# Postmaster.net
KiCad netlist of a schematic drawn in EAGLE
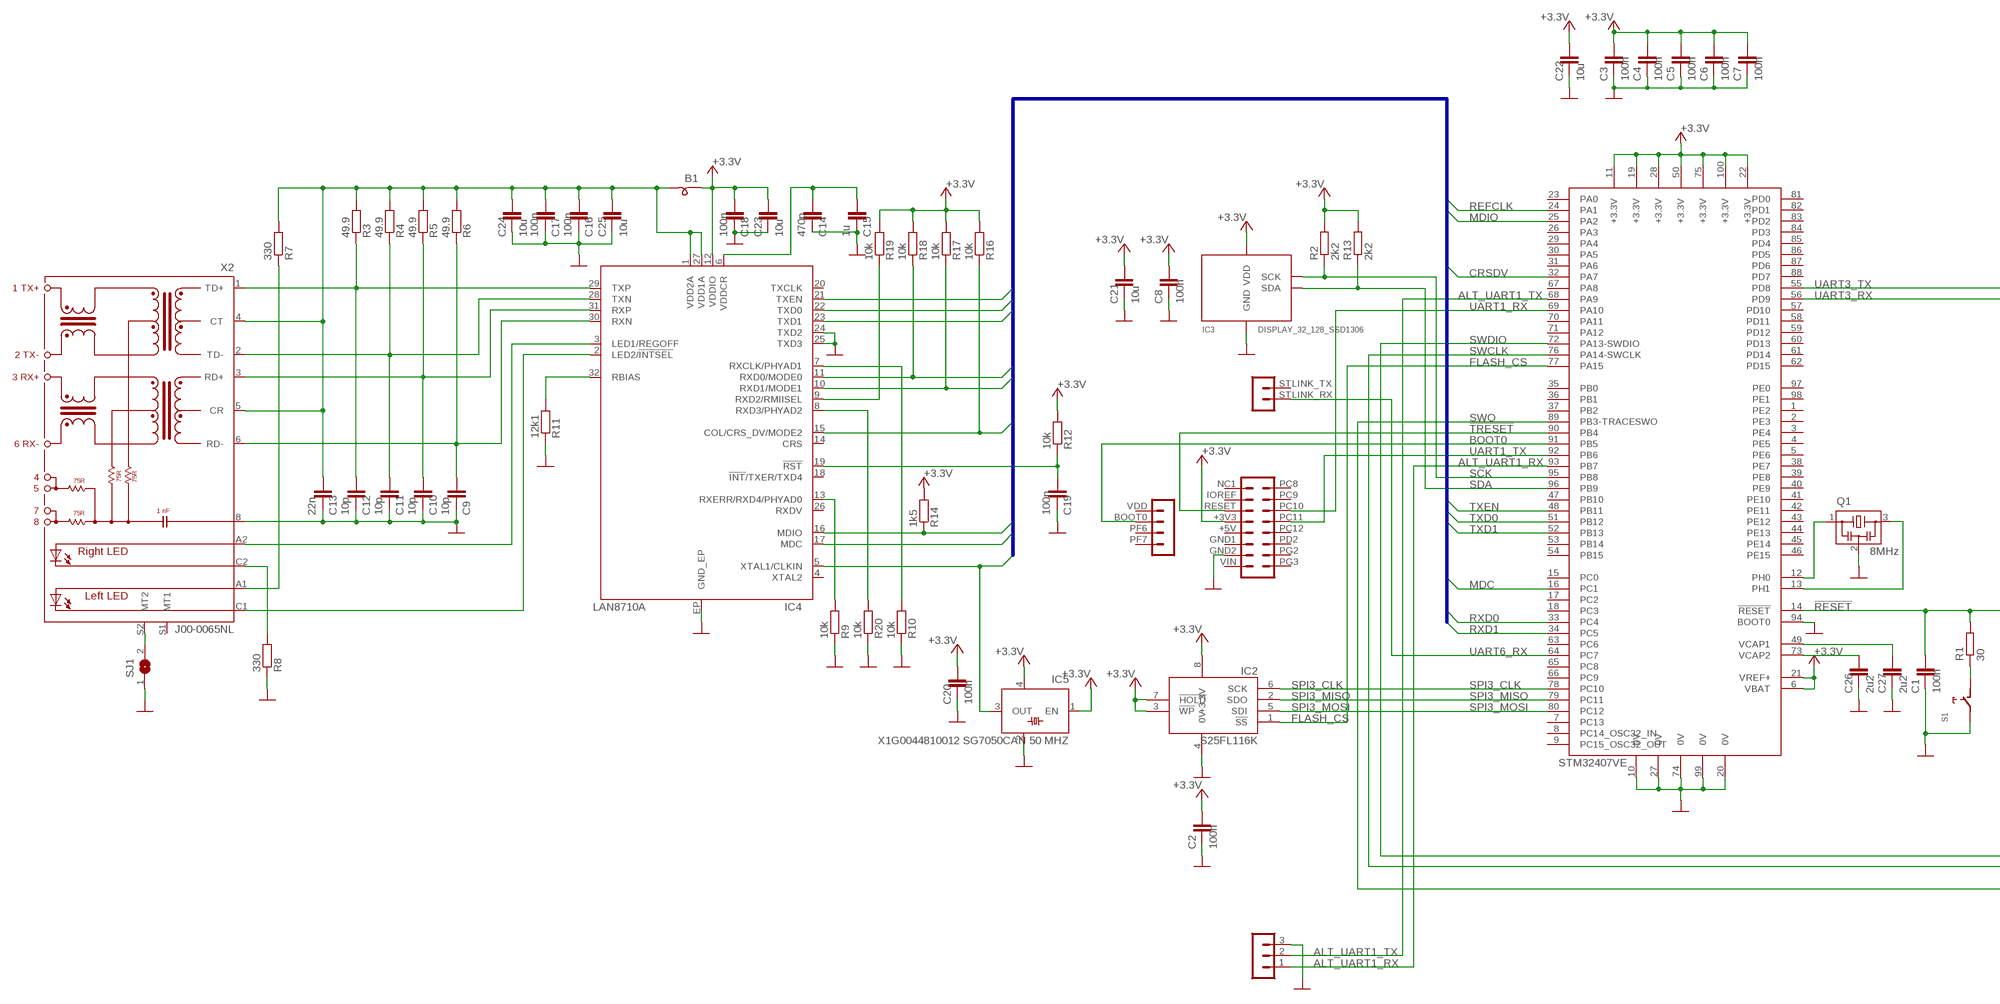
[diagram p0: schematic, sheet 1, part 1 of 2]
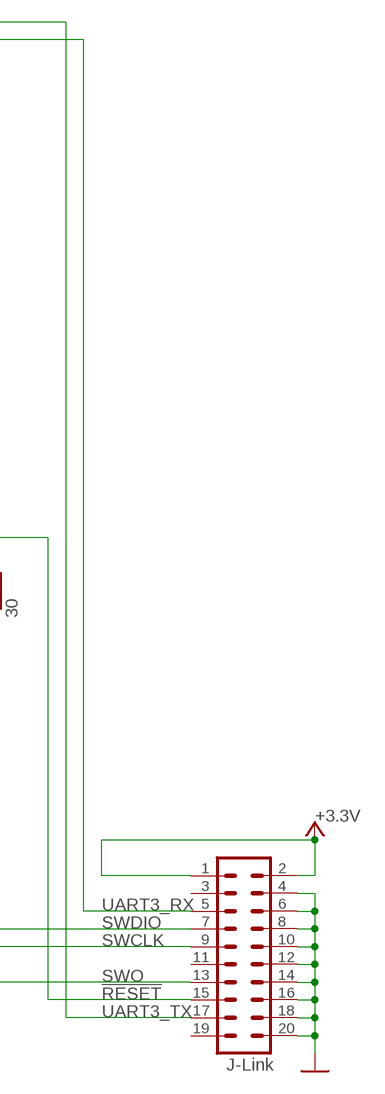
[diagram p1: schematic, sheet 1, part 2 of 2]

(export (version "E")
  (design (tool "Eeschema 10.0.6"))
  (components
    (comp (ref "B1")
      (value "BEADSMD")
      (footprint "eagle-import:0805")
      (libsource (lib "eagle-import") (part "BEADSMD"))
    )
    (comp (ref "C1")
      (value "100n")
      (footprint "eagle-import:0805")
      (libsource (lib "eagle-import") (part "CAPACITOR0805"))
    )
    (comp (ref "C2")
      (value "100n")
      (footprint "eagle-import:0805")
      (libsource (lib "eagle-import") (part "CAPACITOR0805"))
    )
    (comp (ref "C3")
      (value "100n")
      (footprint "eagle-import:0805")
      (libsource (lib "eagle-import") (part "CAPACITOR0805"))
    )
    (comp (ref "C4")
      (value "100n")
      (footprint "eagle-import:0805")
      (libsource (lib "eagle-import") (part "CAPACITOR0805"))
    )
    (comp (ref "C5")
      (value "100n")
      (footprint "eagle-import:0805")
      (libsource (lib "eagle-import") (part "CAPACITOR0805"))
    )
    (comp (ref "C6")
      (value "100n")
      (footprint "eagle-import:0805")
      (libsource (lib "eagle-import") (part "CAPACITOR0805"))
    )
    (comp (ref "C7")
      (value "100n")
      (footprint "eagle-import:0805")
      (libsource (lib "eagle-import") (part "CAPACITOR0805"))
    )
    (comp (ref "C8")
      (value "100n")
      (footprint "eagle-import:0805")
      (libsource (lib "eagle-import") (part "CAPACITOR0805"))
    )
    (comp (ref "C9")
      (value "10p")
      (footprint "eagle-import:0805")
      (libsource (lib "eagle-import") (part "CAPACITOR0805"))
    )
    (comp (ref "C10")
      (value "10p")
      (footprint "eagle-import:0805")
      (libsource (lib "eagle-import") (part "CAPACITOR0805"))
    )
    (comp (ref "C11")
      (value "10p")
      (footprint "eagle-import:0805")
      (libsource (lib "eagle-import") (part "CAPACITOR0805"))
    )
    (comp (ref "C12")
      (value "10p")
      (footprint "eagle-import:0805")
      (libsource (lib "eagle-import") (part "CAPACITOR0805"))
    )
    (comp (ref "C13")
      (value "22n")
      (footprint "eagle-import:0805")
      (libsource (lib "eagle-import") (part "CAPACITOR0805"))
    )
    (comp (ref "C14")
      (value "470p")
      (footprint "eagle-import:0805")
      (libsource (lib "eagle-import") (part "CAPACITOR0805"))
    )
    (comp (ref "C15")
      (value "1u")
      (footprint "eagle-import:0805")
      (libsource (lib "eagle-import") (part "CAPACITOR0805"))
    )
    (comp (ref "C16")
      (value "100n")
      (footprint "eagle-import:0805")
      (libsource (lib "eagle-import") (part "CAPACITOR0805"))
    )
    (comp (ref "C17")
      (value "100n")
      (footprint "eagle-import:0805")
      (libsource (lib "eagle-import") (part "CAPACITOR0805"))
    )
    (comp (ref "C18")
      (value "100n")
      (footprint "eagle-import:0805")
      (libsource (lib "eagle-import") (part "CAPACITOR0805"))
    )
    (comp (ref "C19")
      (value "100n")
      (footprint "eagle-import:0805")
      (libsource (lib "eagle-import") (part "CAPACITOR0805"))
    )
    (comp (ref "C20")
      (value "100n")
      (footprint "eagle-import:0805")
      (libsource (lib "eagle-import") (part "CAPACITOR0805"))
    )
    (comp (ref "C21")
      (value "10u")
      (footprint "eagle-import:0805")
      (libsource (lib "eagle-import") (part "CAPACITOR0805"))
    )
    (comp (ref "C22")
      (value "10u")
      (footprint "eagle-import:0805")
      (libsource (lib "eagle-import") (part "CAPACITOR0805"))
    )
    (comp (ref "C23")
      (value "10u")
      (footprint "eagle-import:0805")
      (libsource (lib "eagle-import") (part "CAPACITOR0805"))
    )
    (comp (ref "C24")
      (value "10u")
      (footprint "eagle-import:0805")
      (libsource (lib "eagle-import") (part "CAPACITOR0805"))
    )
    (comp (ref "C25")
      (value "10u")
      (footprint "eagle-import:0805")
      (libsource (lib "eagle-import") (part "CAPACITOR0805"))
    )
    (comp (ref "C26")
      (value "2u2")
      (footprint "eagle-import:0805")
      (libsource (lib "eagle-import") (part "CAPACITOR0805"))
    )
    (comp (ref "C27")
      (value "2u2")
      (footprint "eagle-import:0805")
      (libsource (lib "eagle-import") (part "CAPACITOR0805"))
    )
    (comp (ref "IC1")
      (value "STM32F407")
      (footprint "eagle-import:TQFP100")
      (libsource (lib "eagle-import") (part "STM32F407"))
    )
    (comp (ref "IC2")
      (value "S25FL116K")
      (footprint "eagle-import:SOIC8-WIDE")
      (libsource (lib "eagle-import") (part "S25FL116KW"))
    )
    (comp (ref "IC3")
      (value "DISPLAY_32_128_SSD1306")
      (footprint "eagle-import:DISPLAY_128_32_SSD1306")
      (libsource (lib "eagle-import") (part "DISPLAY_32_128_SSD1306"))
    )
    (comp (ref "IC4")
      (value "LAN8710A")
      (footprint "eagle-import:QFN32")
      (libsource (lib "eagle-import") (part "LAN8710A"))
    )
    (comp (ref "IC5")
      (value "X1G0044810012 SG7050CAN 50 MHZ")
      (footprint "eagle-import:SM77H")
      (libsource (lib "eagle-import") (part "SM77H"))
    )
    (comp (ref "Q1")
      (value "8MHz")
      (footprint "eagle-import:RESONATOR-SMALL")
      (libsource (lib "eagle-import") (part "RESONATOR-S"))
    )
    (comp (ref "R1")
      (value "30")
      (footprint "eagle-import:0805")
      (libsource (lib "eagle-import") (part "RESISTORR0805"))
    )
    (comp (ref "R2")
      (value "2k2")
      (footprint "eagle-import:0805")
      (libsource (lib "eagle-import") (part "RESISTORR0805"))
    )
    (comp (ref "R3")
      (value "49.9")
      (footprint "eagle-import:0805")
      (libsource (lib "eagle-import") (part "RESISTORR0805"))
    )
    (comp (ref "R4")
      (value "49.9")
      (footprint "eagle-import:0805")
      (libsource (lib "eagle-import") (part "RESISTORR0805"))
    )
    (comp (ref "R5")
      (value "49.9")
      (footprint "eagle-import:0805")
      (libsource (lib "eagle-import") (part "RESISTORR0805"))
    )
    (comp (ref "R6")
      (value "49.9")
      (footprint "eagle-import:0805")
      (libsource (lib "eagle-import") (part "RESISTORR0805"))
    )
    (comp (ref "R7")
      (value "330")
      (footprint "eagle-import:0805")
      (libsource (lib "eagle-import") (part "RESISTORR0805"))
    )
    (comp (ref "R8")
      (value "330")
      (footprint "eagle-import:0805")
      (libsource (lib "eagle-import") (part "RESISTORR0805"))
    )
    (comp (ref "R9")
      (value "10k")
      (footprint "eagle-import:0805")
      (libsource (lib "eagle-import") (part "RESISTORR0805"))
    )
    (comp (ref "R10")
      (value "10k")
      (footprint "eagle-import:0805")
      (libsource (lib "eagle-import") (part "RESISTORR0805"))
    )
    (comp (ref "R11")
      (value "12k1")
      (footprint "eagle-import:0805")
      (libsource (lib "eagle-import") (part "RESISTORR0805"))
    )
    (comp (ref "R12")
      (value "10k")
      (footprint "eagle-import:0805")
      (libsource (lib "eagle-import") (part "RESISTORR0805"))
    )
    (comp (ref "R13")
      (value "2k2")
      (footprint "eagle-import:0805")
      (libsource (lib "eagle-import") (part "RESISTORR0805"))
    )
    (comp (ref "R14")
      (value "1k5")
      (footprint "eagle-import:0805")
      (libsource (lib "eagle-import") (part "RESISTORR0805"))
    )
    (comp (ref "R16")
      (value "10k")
      (footprint "eagle-import:0805")
      (libsource (lib "eagle-import") (part "RESISTORR0805"))
    )
    (comp (ref "R17")
      (value "10k")
      (footprint "eagle-import:0805")
      (libsource (lib "eagle-import") (part "RESISTORR0805"))
    )
    (comp (ref "R18")
      (value "10k")
      (footprint "eagle-import:0805")
      (libsource (lib "eagle-import") (part "RESISTORR0805"))
    )
    (comp (ref "R19")
      (value "10k")
      (footprint "eagle-import:0805")
      (libsource (lib "eagle-import") (part "RESISTORR0805"))
    )
    (comp (ref "R20")
      (value "10k")
      (footprint "eagle-import:0805")
      (libsource (lib "eagle-import") (part "RESISTORR0805"))
    )
    (comp (ref "S1")
      (value "SWITCHSMD")
      (footprint "eagle-import:SWITCH-SMD")
      (libsource (lib "eagle-import") (part "SWITCHSMD"))
    )
    (comp (ref "SJ1") (value "SJ") (footprint "eagle-import:SJ") (libsource (lib "eagle-import") (part "SJ")))
    (comp (ref "U$1")
      (value "NUCLEO-TOPLEFT")
      (footprint "eagle-import:NUCLEO-TOPLEFT")
      (libsource (lib "eagle-import") (part "NUCLEO-TOPLEFT"))
    )
    (comp (ref "U$3")
      (value "HEADER-MALE-3")
      (footprint "eagle-import:HEADER-MALE-3")
      (libsource (lib "eagle-import") (part "HEADER-MALE-3"))
    )
    (comp (ref "X1")
      (value "HEADER-IDC-10-2")
      (footprint "eagle-import:IDC-10_2")
      (libsource (lib "eagle-import") (part "HEADER-IDC-10-2"))
    )
    (comp (ref "X2")
      (value "J00-0065NL")
      (footprint "eagle-import:ETHERNET")
      (libsource (lib "eagle-import") (part "J00-0065NL"))
    )
  )
  (nets
    (net (code "1") (name "+3.3V") (class "Default")
      (node (ref "B1") (pin "1") (pinfunction "1_1") (pintype "passive"))
      (node (ref "C18") (pin "1") (pinfunction "1_1") (pintype "passive"))
      (node (ref "C2") (pin "1") (pinfunction "1_1") (pintype "passive"))
      (node (ref "C20") (pin "1") (pinfunction "1_1") (pintype "passive"))
      (node (ref "C21") (pin "1") (pinfunction "1_1") (pintype "passive"))
      (node (ref "C22") (pin "1") (pinfunction "1_1") (pintype "passive"))
      (node (ref "C23") (pin "1") (pinfunction "1_1") (pintype "passive"))
      (node (ref "C3") (pin "1") (pinfunction "1_1") (pintype "passive"))
      (node (ref "C4") (pin "1") (pinfunction "1_1") (pintype "passive"))
      (node (ref "C5") (pin "1") (pinfunction "1_1") (pintype "passive"))
      (node (ref "C6") (pin "1") (pinfunction "1_1") (pintype "passive"))
      (node (ref "C7") (pin "1") (pinfunction "1_1") (pintype "passive"))
      (node (ref "C8") (pin "1") (pinfunction "1_1") (pintype "passive"))
      (node (ref "IC1") (pin "100") (pinfunction "+3.3V_100") (pintype "power_in"))
      (node (ref "IC1") (pin "11") (pinfunction "+3.3V_11") (pintype "power_in"))
      (node (ref "IC1") (pin "19") (pinfunction "+3.3V_19") (pintype "power_in"))
      (node (ref "IC1") (pin "21") (pinfunction "VREF+_21") (pintype "input"))
      (node (ref "IC1") (pin "22") (pinfunction "+3.3V_22") (pintype "power_in"))
      (node (ref "IC1") (pin "28") (pinfunction "+3.3V_28") (pintype "power_in"))
      (node (ref "IC1") (pin "50") (pinfunction "+3.3V_50") (pintype "power_in"))
      (node (ref "IC1") (pin "6") (pinfunction "VBAT_6") (pintype "input"))
      (node (ref "IC1") (pin "75") (pinfunction "+3.3V_75") (pintype "power_in"))
      (node (ref "IC2") (pin "3") (pinfunction "~{WP}_3") (pintype "passive"))
      (node (ref "IC2") (pin "7") (pinfunction "~{HOLD}_7") (pintype "passive"))
      (node (ref "IC2") (pin "8") (pinfunction "+3.3V_8") (pintype "power_in"))
      (node (ref "IC3") (pin "VCC") (pinfunction "VDD_VCC") (pintype "power_in"))
      (node (ref "IC4") (pin "12") (pinfunction "VDDIO_12") (pintype "power_in"))
      (node (ref "IC5") (pin "1") (pinfunction "EN_1") (pintype "input"))
      (node (ref "IC5") (pin "4") (pinfunction "+3.3V_4") (pintype "power_in"))
      (node (ref "R12") (pin "2") (pinfunction "2_2") (pintype "passive"))
      (node (ref "R13") (pin "2") (pinfunction "2_2") (pintype "passive"))
      (node (ref "R14") (pin "2") (pinfunction "2_2") (pintype "passive"))
      (node (ref "R16") (pin "2") (pinfunction "2_2") (pintype "passive"))
      (node (ref "R17") (pin "2") (pinfunction "2_2") (pintype "passive"))
      (node (ref "R18") (pin "2") (pinfunction "2_2") (pintype "passive"))
      (node (ref "R19") (pin "2") (pinfunction "2_2") (pintype "passive"))
      (node (ref "R2") (pin "2") (pinfunction "2_2") (pintype "passive"))
      (node (ref "U$1") (pin "+3V3") (pinfunction "7_+3V3") (pintype "passive"))
      (node (ref "X1") (pin "1") (pinfunction "1_1") (pintype "passive"))
      (node (ref "X1") (pin "2") (pinfunction "2_2") (pintype "passive"))
    )
    (net (code "2") (name "/ALT_UART1_RX") (class "Default")
      (node (ref "IC1") (pin "93") (pinfunction "PB7_93") (pintype "bidirectional"))
      (node (ref "U$3") (pin "1") (pinfunction "1_1") (pintype "passive"))
    )
    (net (code "3") (name "/ALT_UART1_TX") (class "Default")
      (node (ref "IC1") (pin "68") (pinfunction "PA9_68") (pintype "bidirectional"))
      (node (ref "U$3") (pin "2") (pinfunction "2_2") (pintype "passive"))
    )
    (net (code "4") (name "/BOOT0") (class "Default")
      (node (ref "IC1") (pin "91") (pinfunction "PB5_91") (pintype "bidirectional"))
      (node (ref "U$1") (pin "BOOT0") (pinfunction "2_BOOT0") (pintype "passive"))
    )
    (net (code "5") (name "/CRSDV") (class "Default")
      (node (ref "IC1") (pin "32") (pinfunction "PA7_32") (pintype "bidirectional"))
      (node (ref "IC4") (pin "15") (pinfunction "COL/CRS_DV/MODE2_15") (pintype "bidirectional"))
      (node (ref "R16") (pin "1") (pinfunction "1_1") (pintype "passive"))
    )
    (net (code "6") (name "/FLASH_CS") (class "Default")
      (node (ref "IC1") (pin "77") (pinfunction "PA15_77") (pintype "bidirectional"))
      (node (ref "IC2") (pin "1") (pinfunction "~{SS}_1") (pintype "input"))
    )
    (net (code "7") (name "/MDC") (class "Default")
      (node (ref "IC1") (pin "16") (pinfunction "PC1_16") (pintype "bidirectional"))
      (node (ref "IC4") (pin "17") (pinfunction "MDC_17") (pintype "bidirectional"))
    )
    (net (code "8") (name "/MDIO") (class "Default")
      (node (ref "IC1") (pin "25") (pinfunction "PA2_25") (pintype "bidirectional"))
      (node (ref "IC4") (pin "16") (pinfunction "MDIO_16") (pintype "bidirectional"))
      (node (ref "R14") (pin "1") (pinfunction "1_1") (pintype "passive"))
    )
    (net (code "9") (name "/REFCLK") (class "Default")
      (node (ref "IC1") (pin "24") (pinfunction "PA1_24") (pintype "bidirectional"))
      (node (ref "IC4") (pin "5") (pinfunction "XTAL1/CLKIN_5") (pintype "bidirectional"))
      (node (ref "IC5") (pin "3") (pinfunction "OUT_3") (pintype "output"))
    )
    (net (code "10") (name "/RXD0") (class "Default")
      (node (ref "IC1") (pin "33") (pinfunction "PC4_33") (pintype "bidirectional"))
      (node (ref "IC4") (pin "11") (pinfunction "RXD0/MODE0_11") (pintype "bidirectional"))
      (node (ref "R18") (pin "1") (pinfunction "1_1") (pintype "passive"))
    )
    (net (code "11") (name "/RXD1") (class "Default")
      (node (ref "IC1") (pin "34") (pinfunction "PC5_34") (pintype "bidirectional"))
      (node (ref "IC4") (pin "10") (pinfunction "RXD1/MODE1_10") (pintype "bidirectional"))
      (node (ref "R17") (pin "1") (pinfunction "1_1") (pintype "passive"))
    )
    (net (code "12") (name "/SCK") (class "Default")
      (node (ref "IC1") (pin "95") (pinfunction "PB8_95") (pintype "bidirectional"))
      (node (ref "IC3") (pin "SCK") (pinfunction "SCK_SCK") (pintype "bidirectional"))
      (node (ref "R2") (pin "1") (pinfunction "1_1") (pintype "passive"))
    )
    (net (code "13") (name "/SDA") (class "Default")
      (node (ref "IC1") (pin "96") (pinfunction "PB9_96") (pintype "bidirectional"))
      (node (ref "IC3") (pin "SDA") (pinfunction "SDA_SDA") (pintype "bidirectional"))
      (node (ref "R13") (pin "1") (pinfunction "1_1") (pintype "passive"))
    )
    (net (code "14") (name "/SPI3_CLK") (class "Default")
      (node (ref "IC1") (pin "78") (pinfunction "PC10_78") (pintype "bidirectional"))
      (node (ref "IC2") (pin "6") (pinfunction "SCK_6") (pintype "input"))
    )
    (net (code "15") (name "/SPI3_MISO") (class "Default")
      (node (ref "IC1") (pin "79") (pinfunction "PC11_79") (pintype "bidirectional"))
      (node (ref "IC2") (pin "2") (pinfunction "SDO_2") (pintype "output"))
    )
    (net (code "16") (name "/SPI3_MOSI") (class "Default")
      (node (ref "IC1") (pin "80") (pinfunction "PC12_80") (pintype "bidirectional"))
      (node (ref "IC2") (pin "5") (pinfunction "SDI_5") (pintype "input"))
    )
    (net (code "17") (name "/SWCLK") (class "Default")
      (node (ref "IC1") (pin "76") (pinfunction "PA14-SWCLK_76") (pintype "bidirectional"))
      (node (ref "X1") (pin "9") (pinfunction "9_9") (pintype "passive"))
    )
    (net (code "18") (name "/SWDIO") (class "Default")
      (node (ref "IC1") (pin "72") (pinfunction "PA13-SWDIO_72") (pintype "bidirectional"))
      (node (ref "X1") (pin "7") (pinfunction "7_7") (pintype "passive"))
    )
    (net (code "19") (name "/SWO") (class "Default")
      (node (ref "IC1") (pin "89") (pinfunction "PB3-TRACESWO_89") (pintype "bidirectional"))
      (node (ref "X1") (pin "13") (pinfunction "13_13") (pintype "passive"))
    )
    (net (code "20") (name "/TXD0") (class "Default")
      (node (ref "IC1") (pin "51") (pinfunction "PB12_51") (pintype "bidirectional"))
      (node (ref "IC4") (pin "22") (pinfunction "TXD0_22") (pintype "bidirectional"))
    )
    (net (code "21") (name "/TXD1") (class "Default")
      (node (ref "IC1") (pin "52") (pinfunction "PB13_52") (pintype "bidirectional"))
      (node (ref "IC4") (pin "23") (pinfunction "TXD1_23") (pintype "bidirectional"))
    )
    (net (code "22") (name "/TXEN") (class "Default")
      (node (ref "IC1") (pin "48") (pinfunction "PB11_48") (pintype "bidirectional"))
      (node (ref "IC4") (pin "21") (pinfunction "TXEN_21") (pintype "bidirectional"))
    )
    (net (code "23") (name "/UART1_RX") (class "Default")
      (node (ref "IC1") (pin "69") (pinfunction "PA10_69") (pintype "bidirectional"))
      (node (ref "U$1") (pin "PC10") (pinfunction "6_PC10") (pintype "passive"))
    )
    (net (code "24") (name "/UART1_TX") (class "Default")
      (node (ref "IC1") (pin "92") (pinfunction "PB6_92") (pintype "bidirectional"))
      (node (ref "U$1") (pin "PC11") (pinfunction "8_PC11") (pintype "passive"))
    )
    (net (code "25") (name "/UART3_RX") (class "Default")
      (node (ref "IC1") (pin "56") (pinfunction "PD9_56") (pintype "bidirectional"))
      (node (ref "X1") (pin "5") (pinfunction "5_5") (pintype "passive"))
    )
    (net (code "26") (name "/UART3_TX") (class "Default")
      (node (ref "IC1") (pin "55") (pinfunction "PD8_55") (pintype "bidirectional"))
      (node (ref "X1") (pin "17") (pinfunction "17_17") (pintype "passive"))
    )
    (net (code "27") (name "/UART6_RX") (class "Default")
      (node (ref "IC1") (pin "64") (pinfunction "PC7_64") (pintype "bidirectional"))
      (node (ref "U$1") (pin "STLINK_RX") (pinfunction "1_STLINK_RX") (pintype "passive"))
    )
    (net (code "28") (name "/~{RESET}") (class "Default")
      (node (ref "C1") (pin "1") (pinfunction "1_1") (pintype "passive"))
      (node (ref "IC1") (pin "14") (pinfunction "~{RESET}_14") (pintype "input"))
      (node (ref "R1") (pin "2") (pinfunction "2_2") (pintype "passive"))
      (node (ref "X1") (pin "15") (pinfunction "15_15") (pintype "passive"))
    )
    (net (code "29") (name "/~{TRESET}") (class "Default")
      (node (ref "IC1") (pin "90") (pinfunction "PB4_90") (pintype "bidirectional"))
      (node (ref "U$1") (pin "RESET") (pinfunction "5_RESET") (pintype "passive"))
    )
    (net (code "30") (name "0V") (class "Default")
      (node (ref "C1") (pin "2") (pinfunction "2_2") (pintype "passive"))
      (node (ref "C10") (pin "2") (pinfunction "2_2") (pintype "passive"))
      (node (ref "C11") (pin "2") (pinfunction "2_2") (pintype "passive"))
      (node (ref "C12") (pin "2") (pinfunction "2_2") (pintype "passive"))
      (node (ref "C13") (pin "2") (pinfunction "2_2") (pintype "passive"))
      (node (ref "C14") (pin "2") (pinfunction "2_2") (pintype "passive"))
      (node (ref "C15") (pin "2") (pinfunction "2_2") (pintype "passive"))
      (node (ref "C16") (pin "2") (pinfunction "2_2") (pintype "passive"))
      (node (ref "C17") (pin "2") (pinfunction "2_2") (pintype "passive"))
      (node (ref "C18") (pin "2") (pinfunction "2_2") (pintype "passive"))
      (node (ref "C19") (pin "2") (pinfunction "2_2") (pintype "passive"))
      (node (ref "C2") (pin "2") (pinfunction "2_2") (pintype "passive"))
      (node (ref "C20") (pin "2") (pinfunction "2_2") (pintype "passive"))
      (node (ref "C21") (pin "2") (pinfunction "2_2") (pintype "passive"))
      (node (ref "C22") (pin "2") (pinfunction "2_2") (pintype "passive"))
      (node (ref "C23") (pin "2") (pinfunction "2_2") (pintype "passive"))
      (node (ref "C24") (pin "2") (pinfunction "2_2") (pintype "passive"))
      (node (ref "C25") (pin "2") (pinfunction "2_2") (pintype "passive"))
      (node (ref "C26") (pin "2") (pinfunction "2_2") (pintype "passive"))
      (node (ref "C27") (pin "2") (pinfunction "2_2") (pintype "passive"))
      (node (ref "C3") (pin "2") (pinfunction "2_2") (pintype "passive"))
      (node (ref "C4") (pin "2") (pinfunction "2_2") (pintype "passive"))
      (node (ref "C5") (pin "2") (pinfunction "2_2") (pintype "passive"))
      (node (ref "C6") (pin "2") (pinfunction "2_2") (pintype "passive"))
      (node (ref "C7") (pin "2") (pinfunction "2_2") (pintype "passive"))
      (node (ref "C8") (pin "2") (pinfunction "2_2") (pintype "passive"))
      (node (ref "C9") (pin "2") (pinfunction "2_2") (pintype "passive"))
      (node (ref "IC1") (pin "10") (pinfunction "0V_10") (pintype "power_in"))
      (node (ref "IC1") (pin "20") (pinfunction "0V_20") (pintype "power_in"))
      (node (ref "IC1") (pin "27") (pinfunction "0V_27") (pintype "power_in"))
      (node (ref "IC1") (pin "74") (pinfunction "0V_74") (pintype "power_in"))
      (node (ref "IC1") (pin "94") (pinfunction "BOOT0_94") (pintype "input"))
      (node (ref "IC1") (pin "99") (pinfunction "0V_99") (pintype "power_in"))
      (node (ref "IC2") (pin "4") (pinfunction "0V_4") (pintype "power_in"))
      (node (ref "IC3") (pin "GND") (pinfunction "GND_GND") (pintype "power_in"))
      (node (ref "IC4") (pin "24") (pinfunction "TXD2_24") (pintype "bidirectional"))
      (node (ref "IC4") (pin "25") (pinfunction "TXD3_25") (pintype "bidirectional"))
      (node (ref "IC4") (pin "EP") (pinfunction "GND_EP_EP") (pintype "power_in"))
      (node (ref "IC5") (pin "2") (pinfunction "0V_2") (pintype "power_in"))
      (node (ref "Q1") (pin "2") (pinfunction "2_2") (pintype "passive"))
      (node (ref "R10") (pin "1") (pinfunction "1_1") (pintype "passive"))
      (node (ref "R11") (pin "1") (pinfunction "1_1") (pintype "passive"))
      (node (ref "R20") (pin "1") (pinfunction "1_1") (pintype "passive"))
      (node (ref "R8") (pin "1") (pinfunction "1_1") (pintype "passive"))
      (node (ref "R9") (pin "1") (pinfunction "1_1") (pintype "passive"))
      (node (ref "S1") (pin "3") (pinfunction "2_3") (pintype "passive"))
      (node (ref "S1") (pin "4") (pinfunction "2_4") (pintype "passive"))
      (node (ref "SJ1") (pin "1") (pinfunction "1_1") (pintype "passive"))
      (node (ref "U$1") (pin "GND2") (pinfunction "13_GND2") (pintype "passive"))
      (node (ref "U$3") (pin "3") (pinfunction "3_3") (pintype "passive"))
      (node (ref "X1") (pin "10") (pinfunction "10_10") (pintype "passive"))
      (node (ref "X1") (pin "12") (pinfunction "12_12") (pintype "passive"))
      (node (ref "X1") (pin "14") (pinfunction "14_14") (pintype "passive"))
      (node (ref "X1") (pin "16") (pinfunction "16_16") (pintype "passive"))
      (node (ref "X1") (pin "18") (pinfunction "18_18") (pintype "passive"))
      (node (ref "X1") (pin "20") (pinfunction "20_20") (pintype "passive"))
      (node (ref "X1") (pin "4") (pinfunction "4_4") (pintype "passive"))
      (node (ref "X1") (pin "6") (pinfunction "6_6") (pintype "passive"))
      (node (ref "X1") (pin "8") (pinfunction "8_8") (pintype "passive"))
      (node (ref "X2") (pin "8") (pinfunction "8_8") (pintype "input"))
    )
    (net (code "31") (name "Net-(IC1A-PH0)") (class "Default")
      (node (ref "IC1") (pin "12") (pinfunction "PH0_12") (pintype "bidirectional"))
      (node (ref "Q1") (pin "1") (pinfunction "1_1") (pintype "passive"))
    )
    (net (code "32") (name "Net-(IC1A-PH1)") (class "Default")
      (node (ref "IC1") (pin "13") (pinfunction "PH1_13") (pintype "bidirectional"))
      (node (ref "Q1") (pin "3") (pinfunction "3_3") (pintype "passive"))
    )
    (net (code "33") (name "Net-(IC1A-VCAP1)") (class "Default")
      (node (ref "C27") (pin "1") (pinfunction "1_1") (pintype "passive"))
      (node (ref "IC1") (pin "49") (pinfunction "VCAP1_49") (pintype "bidirectional"))
    )
    (net (code "34") (name "Net-(IC1A-VCAP2)") (class "Default")
      (node (ref "C26") (pin "1") (pinfunction "1_1") (pintype "passive"))
      (node (ref "IC1") (pin "73") (pinfunction "VCAP2_73") (pintype "bidirectional"))
    )
    (net (code "35") (name "Net-(IC4-LED1{slash}REGOFF)") (class "Default")
      (node (ref "IC4") (pin "3") (pinfunction "LED1/REGOFF_3") (pintype "bidirectional"))
      (node (ref "X2") (pin "A2") (pinfunction "A-R_A2") (pintype "passive"))
    )
    (net (code "36") (name "Net-(IC4-LED2{slash}~{INTSEL})") (class "Default")
      (node (ref "IC4") (pin "2") (pinfunction "LED2/~{INTSEL}_2") (pintype "bidirectional"))
      (node (ref "X2") (pin "C1") (pinfunction "C-L_C1") (pintype "passive"))
    )
    (net (code "37") (name "Net-(IC4-RBIAS)") (class "Default")
      (node (ref "IC4") (pin "32") (pinfunction "RBIAS_32") (pintype "bidirectional"))
      (node (ref "R11") (pin "2") (pinfunction "2_2") (pintype "passive"))
    )
    (net (code "38") (name "Net-(IC4-RXCLK{slash}PHYAD1)") (class "Default")
      (node (ref "IC4") (pin "7") (pinfunction "RXCLK/PHYAD1_7") (pintype "bidirectional"))
      (node (ref "R10") (pin "2") (pinfunction "2_2") (pintype "passive"))
    )
    (net (code "39") (name "Net-(IC4-RXD2{slash}RMIISEL)") (class "Default")
      (node (ref "IC4") (pin "9") (pinfunction "RXD2/RMIISEL_9") (pintype "bidirectional"))
      (node (ref "R19") (pin "1") (pinfunction "1_1") (pintype "passive"))
    )
    (net (code "40") (name "Net-(IC4-RXD3{slash}PHYAD2)") (class "Default")
      (node (ref "IC4") (pin "8") (pinfunction "RXD3/PHYAD2_8") (pintype "bidirectional"))
      (node (ref "R20") (pin "2") (pinfunction "2_2") (pintype "passive"))
    )
    (net (code "41") (name "Net-(IC4-RXERR{slash}RXD4{slash}PHYAD0)") (class "Default")
      (node (ref "IC4") (pin "13") (pinfunction "RXERR/RXD4/PHYAD0_13") (pintype "bidirectional"))
      (node (ref "R9") (pin "2") (pinfunction "2_2") (pintype "passive"))
    )
    (net (code "42") (name "Net-(IC4-RXN)") (class "Default")
      (node (ref "C9") (pin "1") (pinfunction "1_1") (pintype "passive"))
      (node (ref "IC4") (pin "30") (pinfunction "RXN_30") (pintype "bidirectional"))
      (node (ref "R6") (pin "1") (pinfunction "1_1") (pintype "passive"))
      (node (ref "X2") (pin "6") (pinfunction "RD-_6") (pintype "input"))
    )
    (net (code "43") (name "Net-(IC4-RXP)") (class "Default")
      (node (ref "C10") (pin "1") (pinfunction "1_1") (pintype "passive"))
      (node (ref "IC4") (pin "31") (pinfunction "RXP_31") (pintype "bidirectional"))
      (node (ref "R5") (pin "1") (pinfunction "1_1") (pintype "passive"))
      (node (ref "X2") (pin "3") (pinfunction "RD+_3") (pintype "input"))
    )
    (net (code "44") (name "Net-(IC4-TXN)") (class "Default")
      (node (ref "C11") (pin "1") (pinfunction "1_1") (pintype "passive"))
      (node (ref "IC4") (pin "28") (pinfunction "TXN_28") (pintype "bidirectional"))
      (node (ref "R4") (pin "1") (pinfunction "1_1") (pintype "passive"))
      (node (ref "X2") (pin "2") (pinfunction "TD-_2") (pintype "input"))
    )
    (net (code "45") (name "Net-(IC4-TXP)") (class "Default")
      (node (ref "C12") (pin "1") (pinfunction "1_1") (pintype "passive"))
      (node (ref "IC4") (pin "29") (pinfunction "TXP_29") (pintype "bidirectional"))
      (node (ref "R3") (pin "1") (pinfunction "1_1") (pintype "passive"))
      (node (ref "X2") (pin "1") (pinfunction "TD+_1") (pintype "input"))
    )
    (net (code "46") (name "Net-(IC4-VDD1A)") (class "Default")
      (node (ref "B1") (pin "2") (pinfunction "2_2") (pintype "passive"))
      (node (ref "C13") (pin "1") (pinfunction "1_1") (pintype "passive"))
      (node (ref "C16") (pin "1") (pinfunction "1_1") (pintype "passive"))
      (node (ref "C17") (pin "1") (pinfunction "1_1") (pintype "passive"))
      (node (ref "C24") (pin "1") (pinfunction "1_1") (pintype "passive"))
      (node (ref "C25") (pin "1") (pinfunction "1_1") (pintype "passive"))
      (node (ref "IC4") (pin "1") (pinfunction "VDD2A_1") (pintype "power_in"))
      (node (ref "IC4") (pin "27") (pinfunction "VDD1A_27") (pintype "power_in"))
      (node (ref "R3") (pin "2") (pinfunction "2_2") (pintype "passive"))
      (node (ref "R4") (pin "2") (pinfunction "2_2") (pintype "passive"))
      (node (ref "R5") (pin "2") (pinfunction "2_2") (pintype "passive"))
      (node (ref "R6") (pin "2") (pinfunction "2_2") (pintype "passive"))
      (node (ref "R7") (pin "2") (pinfunction "2_2") (pintype "passive"))
      (node (ref "X2") (pin "4") (pinfunction "CT_4") (pintype "input"))
      (node (ref "X2") (pin "5") (pinfunction "CR_5") (pintype "input"))
    )
    (net (code "47") (name "Net-(IC4-VDDCR)") (class "Default")
      (node (ref "C14") (pin "1") (pinfunction "1_1") (pintype "passive"))
      (node (ref "C15") (pin "1") (pinfunction "1_1") (pintype "passive"))
      (node (ref "IC4") (pin "6") (pinfunction "VDDCR_6") (pintype "power_in"))
    )
    (net (code "48") (name "Net-(IC4-~{RST})") (class "Default")
      (node (ref "C19") (pin "1") (pinfunction "1_1") (pintype "passive"))
      (node (ref "IC4") (pin "19") (pinfunction "~{RST}_19") (pintype "bidirectional"))
      (node (ref "R12") (pin "1") (pinfunction "1_1") (pintype "passive"))
    )
    (net (code "49") (name "Net-(R1-Pad1)") (class "Default")
      (node (ref "R1") (pin "1") (pinfunction "1_1") (pintype "passive"))
      (node (ref "S1") (pin "1") (pinfunction "1_1") (pintype "passive"))
      (node (ref "S1") (pin "2") (pinfunction "1_2") (pintype "passive"))
    )
    (net (code "50") (name "Net-(X2-A-L)") (class "Default")
      (node (ref "R7") (pin "1") (pinfunction "1_1") (pintype "passive"))
      (node (ref "X2") (pin "A1") (pinfunction "A-L_A1") (pintype "passive"))
    )
    (net (code "51") (name "Net-(X2-C-R)") (class "Default")
      (node (ref "R8") (pin "2") (pinfunction "2_2") (pintype "passive"))
      (node (ref "X2") (pin "C2") (pinfunction "C-R_C2") (pintype "passive"))
    )
    (net (code "52") (name "Net-(X2-MT2)") (class "Default")
      (node (ref "SJ1") (pin "2") (pinfunction "2_2") (pintype "passive"))
      (node (ref "X2") (pin "S2") (pinfunction "MT2_S2") (pintype "bidirectional"))
    )
    (net (code "53") (name "unconnected-(IC1A-PA0-Pad23)") (class "Default")
      (node (ref "IC1") (pin "23") (pinfunction "PA0_23") (pintype "bidirectional"))
    )
    (net (code "54") (name "unconnected-(IC1A-PA3-Pad26)") (class "Default")
      (node (ref "IC1") (pin "26") (pinfunction "PA3_26") (pintype "bidirectional"))
    )
    (net (code "55") (name "unconnected-(IC1A-PA4-Pad29)") (class "Default")
      (node (ref "IC1") (pin "29") (pinfunction "PA4_29") (pintype "bidirectional"))
    )
    (net (code "56") (name "unconnected-(IC1A-PA5-Pad30)") (class "Default")
      (node (ref "IC1") (pin "30") (pinfunction "PA5_30") (pintype "bidirectional"))
    )
    (net (code "57") (name "unconnected-(IC1A-PA6-Pad31)") (class "Default")
      (node (ref "IC1") (pin "31") (pinfunction "PA6_31") (pintype "bidirectional"))
    )
    (net (code "58") (name "unconnected-(IC1A-PA8-Pad67)") (class "Default")
      (node (ref "IC1") (pin "67") (pinfunction "PA8_67") (pintype "bidirectional"))
    )
    (net (code "59") (name "unconnected-(IC1A-PA11-Pad70)") (class "Default")
      (node (ref "IC1") (pin "70") (pinfunction "PA11_70") (pintype "bidirectional"))
    )
    (net (code "60") (name "unconnected-(IC1A-PA12-Pad71)") (class "Default")
      (node (ref "IC1") (pin "71") (pinfunction "PA12_71") (pintype "bidirectional"))
    )
    (net (code "61") (name "unconnected-(IC1A-PB0-Pad35)") (class "Default")
      (node (ref "IC1") (pin "35") (pinfunction "PB0_35") (pintype "bidirectional"))
    )
    (net (code "62") (name "unconnected-(IC1A-PB1-Pad36)") (class "Default")
      (node (ref "IC1") (pin "36") (pinfunction "PB1_36") (pintype "bidirectional"))
    )
    (net (code "63") (name "unconnected-(IC1A-PB2-Pad37)") (class "Default")
      (node (ref "IC1") (pin "37") (pinfunction "PB2_37") (pintype "bidirectional"))
    )
    (net (code "64") (name "unconnected-(IC1A-PB10-Pad47)") (class "Default")
      (node (ref "IC1") (pin "47") (pinfunction "PB10_47") (pintype "bidirectional"))
    )
    (net (code "65") (name "unconnected-(IC1A-PB14-Pad53)") (class "Default")
      (node (ref "IC1") (pin "53") (pinfunction "PB14_53") (pintype "bidirectional"))
    )
    (net (code "66") (name "unconnected-(IC1A-PB15-Pad54)") (class "Default")
      (node (ref "IC1") (pin "54") (pinfunction "PB15_54") (pintype "bidirectional"))
    )
    (net (code "67") (name "unconnected-(IC1A-PC0-Pad15)") (class "Default")
      (node (ref "IC1") (pin "15") (pinfunction "PC0_15") (pintype "bidirectional"))
    )
    (net (code "68") (name "unconnected-(IC1A-PC2-Pad17)") (class "Default")
      (node (ref "IC1") (pin "17") (pinfunction "PC2_17") (pintype "bidirectional"))
    )
    (net (code "69") (name "unconnected-(IC1A-PC3-Pad18)") (class "Default")
      (node (ref "IC1") (pin "18") (pinfunction "PC3_18") (pintype "bidirectional"))
    )
    (net (code "70") (name "unconnected-(IC1A-PC6-Pad63)") (class "Default")
      (node (ref "IC1") (pin "63") (pinfunction "PC6_63") (pintype "bidirectional"))
    )
    (net (code "71") (name "unconnected-(IC1A-PC8-Pad65)") (class "Default")
      (node (ref "IC1") (pin "65") (pinfunction "PC8_65") (pintype "bidirectional"))
    )
    (net (code "72") (name "unconnected-(IC1A-PC9-Pad66)") (class "Default")
      (node (ref "IC1") (pin "66") (pinfunction "PC9_66") (pintype "bidirectional"))
    )
    (net (code "73") (name "unconnected-(IC1A-PC13-Pad7)") (class "Default")
      (node (ref "IC1") (pin "7") (pinfunction "PC13_7") (pintype "bidirectional"))
    )
    (net (code "74") (name "unconnected-(IC1A-PC14_OSC32_IN-Pad8)") (class "Default")
      (node (ref "IC1") (pin "8") (pinfunction "PC14_OSC32_IN_8") (pintype "bidirectional"))
    )
    (net (code "75") (name "unconnected-(IC1A-PC15_OSC32_OUT-Pad9)") (class "Default")
      (node (ref "IC1") (pin "9") (pinfunction "PC15_OSC32_OUT_9") (pintype "bidirectional"))
    )
    (net (code "76") (name "unconnected-(IC1A-PD0-Pad81)") (class "Default")
      (node (ref "IC1") (pin "81") (pinfunction "PD0_81") (pintype "bidirectional"))
    )
    (net (code "77") (name "unconnected-(IC1A-PD1-Pad82)") (class "Default")
      (node (ref "IC1") (pin "82") (pinfunction "PD1_82") (pintype "bidirectional"))
    )
    (net (code "78") (name "unconnected-(IC1A-PD2-Pad83)") (class "Default")
      (node (ref "IC1") (pin "83") (pinfunction "PD2_83") (pintype "bidirectional"))
    )
    (net (code "79") (name "unconnected-(IC1A-PD3-Pad84)") (class "Default")
      (node (ref "IC1") (pin "84") (pinfunction "PD3_84") (pintype "bidirectional"))
    )
    (net (code "80") (name "unconnected-(IC1A-PD4-Pad85)") (class "Default")
      (node (ref "IC1") (pin "85") (pinfunction "PD4_85") (pintype "bidirectional"))
    )
    (net (code "81") (name "unconnected-(IC1A-PD5-Pad86)") (class "Default")
      (node (ref "IC1") (pin "86") (pinfunction "PD5_86") (pintype "bidirectional"))
    )
    (net (code "82") (name "unconnected-(IC1A-PD6-Pad87)") (class "Default")
      (node (ref "IC1") (pin "87") (pinfunction "PD6_87") (pintype "bidirectional"))
    )
    (net (code "83") (name "unconnected-(IC1A-PD7-Pad88)") (class "Default")
      (node (ref "IC1") (pin "88") (pinfunction "PD7_88") (pintype "bidirectional"))
    )
    (net (code "84") (name "unconnected-(IC1A-PD10-Pad57)") (class "Default")
      (node (ref "IC1") (pin "57") (pinfunction "PD10_57") (pintype "bidirectional"))
    )
    (net (code "85") (name "unconnected-(IC1A-PD11-Pad58)") (class "Default")
      (node (ref "IC1") (pin "58") (pinfunction "PD11_58") (pintype "bidirectional"))
    )
    (net (code "86") (name "unconnected-(IC1A-PD12-Pad59)") (class "Default")
      (node (ref "IC1") (pin "59") (pinfunction "PD12_59") (pintype "bidirectional"))
    )
    (net (code "87") (name "unconnected-(IC1A-PD13-Pad60)") (class "Default")
      (node (ref "IC1") (pin "60") (pinfunction "PD13_60") (pintype "bidirectional"))
    )
    (net (code "88") (name "unconnected-(IC1A-PD14-Pad61)") (class "Default")
      (node (ref "IC1") (pin "61") (pinfunction "PD14_61") (pintype "bidirectional"))
    )
    (net (code "89") (name "unconnected-(IC1A-PD15-Pad62)") (class "Default")
      (node (ref "IC1") (pin "62") (pinfunction "PD15_62") (pintype "bidirectional"))
    )
    (net (code "90") (name "unconnected-(IC1A-PE0-Pad97)") (class "Default")
      (node (ref "IC1") (pin "97") (pinfunction "PE0_97") (pintype "bidirectional"))
    )
    (net (code "91") (name "unconnected-(IC1A-PE1-Pad98)") (class "Default")
      (node (ref "IC1") (pin "98") (pinfunction "PE1_98") (pintype "bidirectional"))
    )
    (net (code "92") (name "unconnected-(IC1A-PE2-Pad1)") (class "Default")
      (node (ref "IC1") (pin "1") (pinfunction "PE2_1") (pintype "bidirectional"))
    )
    (net (code "93") (name "unconnected-(IC1A-PE3-Pad2)") (class "Default")
      (node (ref "IC1") (pin "2") (pinfunction "PE3_2") (pintype "bidirectional"))
    )
    (net (code "94") (name "unconnected-(IC1A-PE4-Pad3)") (class "Default")
      (node (ref "IC1") (pin "3") (pinfunction "PE4_3") (pintype "bidirectional"))
    )
    (net (code "95") (name "unconnected-(IC1A-PE5-Pad4)") (class "Default")
      (node (ref "IC1") (pin "4") (pinfunction "PE5_4") (pintype "bidirectional"))
    )
    (net (code "96") (name "unconnected-(IC1A-PE6-Pad5)") (class "Default")
      (node (ref "IC1") (pin "5") (pinfunction "PE6_5") (pintype "bidirectional"))
    )
    (net (code "97") (name "unconnected-(IC1A-PE7-Pad38)") (class "Default")
      (node (ref "IC1") (pin "38") (pinfunction "PE7_38") (pintype "bidirectional"))
    )
    (net (code "98") (name "unconnected-(IC1A-PE8-Pad39)") (class "Default")
      (node (ref "IC1") (pin "39") (pinfunction "PE8_39") (pintype "bidirectional"))
    )
    (net (code "99") (name "unconnected-(IC1A-PE9-Pad40)") (class "Default")
      (node (ref "IC1") (pin "40") (pinfunction "PE9_40") (pintype "bidirectional"))
    )
    (net (code "100") (name "unconnected-(IC1A-PE10-Pad41)") (class "Default")
      (node (ref "IC1") (pin "41") (pinfunction "PE10_41") (pintype "bidirectional"))
    )
    (net (code "101") (name "unconnected-(IC1A-PE11-Pad42)") (class "Default")
      (node (ref "IC1") (pin "42") (pinfunction "PE11_42") (pintype "bidirectional"))
    )
    (net (code "102") (name "unconnected-(IC1A-PE12-Pad43)") (class "Default")
      (node (ref "IC1") (pin "43") (pinfunction "PE12_43") (pintype "bidirectional"))
    )
    (net (code "103") (name "unconnected-(IC1A-PE13-Pad44)") (class "Default")
      (node (ref "IC1") (pin "44") (pinfunction "PE13_44") (pintype "bidirectional"))
    )
    (net (code "104") (name "unconnected-(IC1A-PE14-Pad45)") (class "Default")
      (node (ref "IC1") (pin "45") (pinfunction "PE14_45") (pintype "bidirectional"))
    )
    (net (code "105") (name "unconnected-(IC1A-PE15-Pad46)") (class "Default")
      (node (ref "IC1") (pin "46") (pinfunction "PE15_46") (pintype "bidirectional"))
    )
    (net (code "106") (name "unconnected-(IC4-CRS-Pad14)") (class "Default")
      (node (ref "IC4") (pin "14") (pinfunction "CRS_14") (pintype "bidirectional"))
    )
    (net (code "107") (name "unconnected-(IC4-RXDV-Pad26)") (class "Default")
      (node (ref "IC4") (pin "26") (pinfunction "RXDV_26") (pintype "bidirectional"))
    )
    (net (code "108") (name "unconnected-(IC4-TXCLK-Pad20)") (class "Default")
      (node (ref "IC4") (pin "20") (pinfunction "TXCLK_20") (pintype "bidirectional"))
    )
    (net (code "109") (name "unconnected-(IC4-XTAL2-Pad4)") (class "Default")
      (node (ref "IC4") (pin "4") (pinfunction "XTAL2_4") (pintype "bidirectional"))
    )
    (net (code "110") (name "unconnected-(IC4-~{INT}{slash}TXER{slash}TXD4-Pad18)") (class "Default")
      (node (ref "IC4") (pin "18") (pinfunction "~{INT}/TXER/TXD4_18") (pintype "bidirectional"))
    )
    (net (code "111") (name "unconnected-(U$1A-1-PadVDD)") (class "Default")
      (node (ref "U$1") (pin "VDD") (pinfunction "1_VDD") (pintype "passive"))
    )
    (net (code "112") (name "unconnected-(U$1A-3-PadPF6)") (class "Default")
      (node (ref "U$1") (pin "PF6") (pinfunction "3_PF6") (pintype "passive"))
    )
    (net (code "113") (name "unconnected-(U$1A-4-PadPF7)") (class "Default")
      (node (ref "U$1") (pin "PF7") (pinfunction "4_PF7") (pintype "passive"))
    )
    (net (code "114") (name "unconnected-(U$1B-1-PadNC1)") (class "Default")
      (node (ref "U$1") (pin "NC1") (pinfunction "1_NC1") (pintype "passive"))
    )
    (net (code "115") (name "unconnected-(U$1B-2-PadPC8)") (class "Default")
      (node (ref "U$1") (pin "PC8") (pinfunction "2_PC8") (pintype "passive"))
    )
    (net (code "116") (name "unconnected-(U$1B-3-PadIOREF)") (class "Default")
      (node (ref "U$1") (pin "IOREF") (pinfunction "3_IOREF") (pintype "passive"))
    )
    (net (code "117") (name "unconnected-(U$1B-4-PadPC9)") (class "Default")
      (node (ref "U$1") (pin "PC9") (pinfunction "4_PC9") (pintype "passive"))
    )
    (net (code "118") (name "unconnected-(U$1B-9-Pad+5V)") (class "Default")
      (node (ref "U$1") (pin "+5V") (pinfunction "9_+5V") (pintype "passive"))
    )
    (net (code "119") (name "unconnected-(U$1B-10-PadPC12)") (class "Default")
      (node (ref "U$1") (pin "PC12") (pinfunction "10_PC12") (pintype "passive"))
    )
    (net (code "120") (name "unconnected-(U$1B-11-PadGND1)") (class "Default")
      (node (ref "U$1") (pin "GND1") (pinfunction "11_GND1") (pintype "passive"))
    )
    (net (code "121") (name "unconnected-(U$1B-12-PadPD2)") (class "Default")
      (node (ref "U$1") (pin "PD2") (pinfunction "12_PD2") (pintype "passive"))
    )
    (net (code "122") (name "unconnected-(U$1B-14-PadPG2)") (class "Default")
      (node (ref "U$1") (pin "PG2") (pinfunction "14_PG2") (pintype "passive"))
    )
    (net (code "123") (name "unconnected-(U$1B-15-PadVIN)") (class "Default")
      (node (ref "U$1") (pin "VIN") (pinfunction "15_VIN") (pintype "passive"))
    )
    (net (code "124") (name "unconnected-(U$1B-16-PadPG3)") (class "Default")
      (node (ref "U$1") (pin "PG3") (pinfunction "16_PG3") (pintype "passive"))
    )
    (net (code "125") (name "unconnected-(U$1C-2-PadSTLINK_TX)") (class "Default")
      (node (ref "U$1") (pin "STLINK_TX") (pinfunction "2_STLINK_TX") (pintype "passive"))
    )
    (net (code "126") (name "unconnected-(X1-Pad3)") (class "Default")
      (node (ref "X1") (pin "3") (pinfunction "3_3") (pintype "passive"))
    )
    (net (code "127") (name "unconnected-(X1-Pad11)") (class "Default")
      (node (ref "X1") (pin "11") (pinfunction "11_11") (pintype "passive"))
    )
    (net (code "128") (name "unconnected-(X1-Pad19)") (class "Default")
      (node (ref "X1") (pin "19") (pinfunction "19_19") (pintype "passive"))
    )
    (net (code "129") (name "unconnected-(X2-MT1-PadS1)") (class "Default")
      (node (ref "X2") (pin "S1") (pinfunction "MT1_S1") (pintype "bidirectional"))
    )
  )
)
